# lighting_schematic.net
KiCad netlist of a schematic drawn in EasyEDA
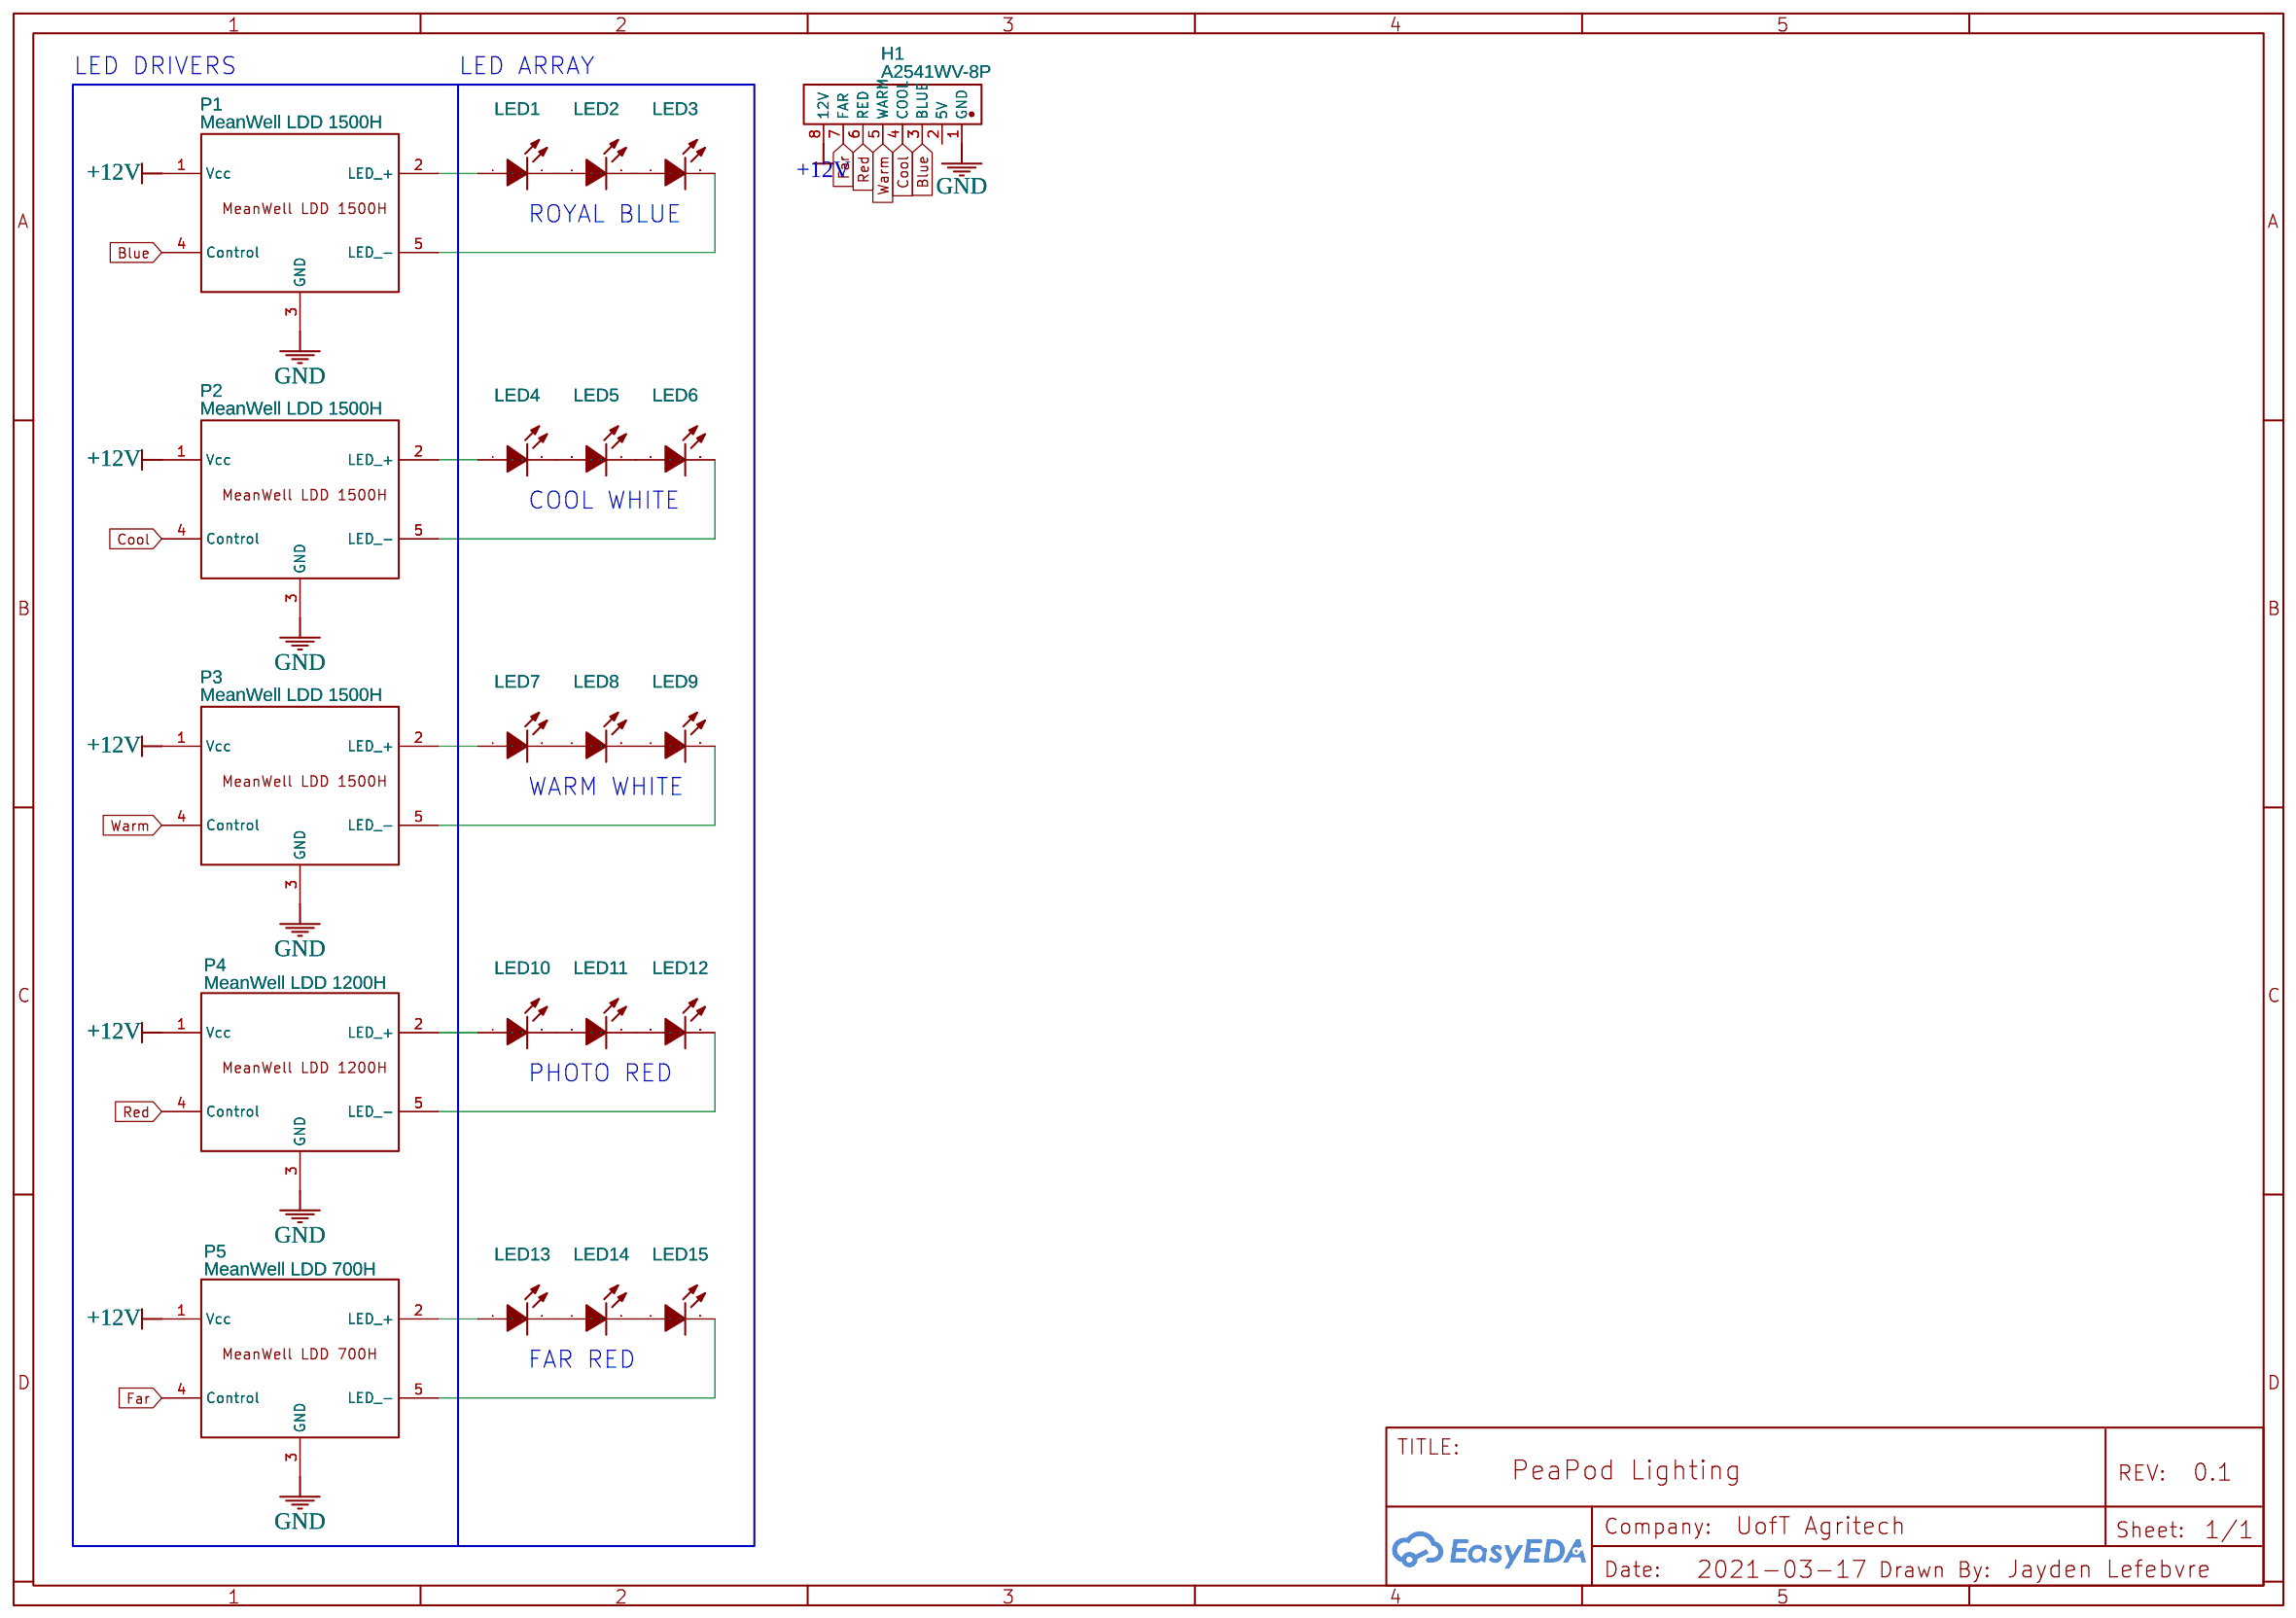
[diagram p0: schematic sheet]

(export (version "E")
  (design (tool "Eeschema 10.0.6"))
  (components
    (comp (ref "H1")
      (value "A2541WV-8P")
      (fields (field (name "BOM_Supplier Part") "C225483"))
      (libsource (lib "") (part "A2541WV-8P"))
    )
    (comp (ref "LED1")
      (value "XLAMP XP-G3 LED")
      (fields (field (name "BOM_Manufacturer Part") "XPGDWT-01-0000-00ME3"))
      (libsource (lib "") (part "XLAMP XP-G3 LED"))
    )
    (comp (ref "LED2")
      (value "XLAMP XP-G3 LED")
      (fields (field (name "BOM_Manufacturer Part") "XPGDWT-01-0000-00ME3"))
      (libsource (lib "") (part "XLAMP XP-G3 LED"))
    )
    (comp (ref "LED3")
      (value "XLAMP XP-G3 LED")
      (fields (field (name "BOM_Manufacturer Part") "XPGDWT-01-0000-00ME3"))
      (libsource (lib "") (part "XLAMP XP-G3 LED"))
    )
    (comp (ref "LED4")
      (value "XLAMP XP-G3 LED")
      (fields (field (name "BOM_Manufacturer Part") "XPGDWT-01-0000-00ME3"))
      (libsource (lib "") (part "XLAMP XP-G3 LED"))
    )
    (comp (ref "LED5")
      (value "XLAMP XP-G3 LED")
      (fields (field (name "BOM_Manufacturer Part") "XPGDWT-01-0000-00ME3"))
      (libsource (lib "") (part "XLAMP XP-G3 LED"))
    )
    (comp (ref "LED6")
      (value "XLAMP XP-G3 LED")
      (fields (field (name "BOM_Manufacturer Part") "XPGDWT-01-0000-00ME3"))
      (libsource (lib "") (part "XLAMP XP-G3 LED"))
    )
    (comp (ref "LED7")
      (value "XLAMP XP-G3 LED")
      (fields (field (name "BOM_Manufacturer Part") "XPGDWT-01-0000-00ME3"))
      (libsource (lib "") (part "XLAMP XP-G3 LED"))
    )
    (comp (ref "LED8")
      (value "XLAMP XP-G3 LED")
      (fields (field (name "BOM_Manufacturer Part") "XPGDWT-01-0000-00ME3"))
      (libsource (lib "") (part "XLAMP XP-G3 LED"))
    )
    (comp (ref "LED9")
      (value "XLAMP XP-G3 LED")
      (fields (field (name "BOM_Manufacturer Part") "XPGDWT-01-0000-00ME3"))
      (libsource (lib "") (part "XLAMP XP-G3 LED"))
    )
    (comp (ref "LED10")
      (value "XLAMP XP-G3 LED")
      (fields (field (name "BOM_Manufacturer Part") "XPGDWT-01-0000-00ME3"))
      (libsource (lib "") (part "XLAMP XP-G3 LED"))
    )
    (comp (ref "LED11")
      (value "XLAMP XP-G3 LED")
      (fields (field (name "BOM_Manufacturer Part") "XPGDWT-01-0000-00ME3"))
      (libsource (lib "") (part "XLAMP XP-G3 LED"))
    )
    (comp (ref "LED12")
      (value "XLAMP XP-G3 LED")
      (fields (field (name "BOM_Manufacturer Part") "XPGDWT-01-0000-00ME3"))
      (libsource (lib "") (part "XLAMP XP-G3 LED"))
    )
    (comp (ref "LED13")
      (value "XLAMP XP-G3 LED")
      (fields (field (name "BOM_Manufacturer Part") "XPGDWT-01-0000-00ME3"))
      (libsource (lib "") (part "XLAMP XP-G3 LED"))
    )
    (comp (ref "LED14")
      (value "XLAMP XP-G3 LED")
      (fields (field (name "BOM_Manufacturer Part") "XPGDWT-01-0000-00ME3"))
      (libsource (lib "") (part "XLAMP XP-G3 LED"))
    )
    (comp (ref "LED15")
      (value "XLAMP XP-G3 LED")
      (fields (field (name "BOM_Manufacturer Part") "XPGDWT-01-0000-00ME3"))
      (libsource (lib "") (part "XLAMP XP-G3 LED"))
    )
    (comp (ref "P1")
      (value "MeanWell LDD 1500H")
      (fields
        (field (name "BOM_Manufacturer Part") "LDD-1500H")
        (field (name "BOM_Supplier Part") "1866-3099-ND")
      )
      (libsource (lib "") (part "MeanWell LDD 1500H"))
    )
    (comp (ref "P2")
      (value "MeanWell LDD 1500H")
      (fields
        (field (name "BOM_Manufacturer Part") "LDD-1500H")
        (field (name "BOM_Supplier Part") "1866-3099-ND")
      )
      (libsource (lib "") (part "MeanWell LDD 1500H"))
    )
    (comp (ref "P3")
      (value "MeanWell LDD 1500H")
      (fields
        (field (name "BOM_Manufacturer Part") "LDD-1500H")
        (field (name "BOM_Supplier Part") "1866-3099-ND")
      )
      (libsource (lib "") (part "MeanWell LDD 1500H"))
    )
    (comp (ref "P4")
      (value "MeanWell LDD 1200H")
      (fields
        (field (name "BOM_Manufacturer Part") "LDD-1200H")
        (field (name "BOM_Supplier Part") "1866-3095-ND")
      )
      (libsource (lib "") (part "MeanWell LDD 1200H"))
    )
    (comp (ref "P5")
      (value "MeanWell LDD 700H")
      (fields
        (field (name "BOM_Manufacturer Part") "LDD-700H")
        (field (name "BOM_Supplier Part") "1866-3119-ND")
      )
      (libsource (lib "") (part "MeanWell LDD 700H"))
    )
  )
  (nets
    (net (code "1") (name "+12V") (class "Default")
      (node (ref "H1") (pin "8") (pinfunction "12V_8") (pintype "unspecified"))
      (node (ref "P1") (pin "1") (pinfunction "Vcc_1") (pintype "unspecified"))
      (node (ref "P2") (pin "1") (pinfunction "Vcc_1") (pintype "unspecified"))
      (node (ref "P3") (pin "1") (pinfunction "Vcc_1") (pintype "unspecified"))
      (node (ref "P4") (pin "1") (pinfunction "Vcc_1") (pintype "unspecified"))
      (node (ref "P5") (pin "1") (pinfunction "Vcc_1") (pintype "unspecified"))
    )
    (net (code "2") (name "Blue") (class "Default")
      (node (ref "H1") (pin "3") (pinfunction "BLUE_3") (pintype "unspecified"))
      (node (ref "P1") (pin "4") (pinfunction "Control_4") (pintype "unspecified"))
    )
    (net (code "3") (name "Cool") (class "Default")
      (node (ref "H1") (pin "4") (pinfunction "COOL_4") (pintype "unspecified"))
      (node (ref "P2") (pin "4") (pinfunction "Control_4") (pintype "unspecified"))
    )
    (net (code "4") (name "Far") (class "Default")
      (node (ref "H1") (pin "7") (pinfunction "FAR_7") (pintype "unspecified"))
      (node (ref "P5") (pin "4") (pinfunction "Control_4") (pintype "unspecified"))
    )
    (net (code "5") (name "GND") (class "Default")
      (node (ref "H1") (pin "1") (pinfunction "GND_1") (pintype "unspecified"))
      (node (ref "P1") (pin "3") (pinfunction "GND_3") (pintype "unspecified"))
      (node (ref "P2") (pin "3") (pinfunction "GND_3") (pintype "unspecified"))
      (node (ref "P3") (pin "3") (pinfunction "GND_3") (pintype "unspecified"))
      (node (ref "P4") (pin "3") (pinfunction "GND_3") (pintype "unspecified"))
      (node (ref "P5") (pin "3") (pinfunction "GND_3") (pintype "unspecified"))
    )
    (net (code "6") (name "Net-(LED1-A)") (class "Default")
      (node (ref "LED1") (pin "1") (pinfunction "A_1") (pintype "unspecified"))
      (node (ref "P1") (pin "2") (pinfunction "LED_+_2") (pintype "unspecified"))
    )
    (net (code "7") (name "Net-(LED1-K)") (class "Default")
      (node (ref "LED1") (pin "2") (pinfunction "K_2") (pintype "unspecified"))
      (node (ref "LED2") (pin "1") (pinfunction "A_1") (pintype "unspecified"))
    )
    (net (code "8") (name "Net-(LED2-K)") (class "Default")
      (node (ref "LED2") (pin "2") (pinfunction "K_2") (pintype "unspecified"))
      (node (ref "LED3") (pin "1") (pinfunction "A_1") (pintype "unspecified"))
    )
    (net (code "9") (name "Net-(LED3-K)") (class "Default")
      (node (ref "LED3") (pin "2") (pinfunction "K_2") (pintype "unspecified"))
      (node (ref "P1") (pin "5") (pinfunction "LED_-_5") (pintype "unspecified"))
    )
    (net (code "10") (name "Net-(LED4-A)") (class "Default")
      (node (ref "LED4") (pin "1") (pinfunction "A_1") (pintype "unspecified"))
      (node (ref "P2") (pin "2") (pinfunction "LED_+_2") (pintype "unspecified"))
    )
    (net (code "11") (name "Net-(LED4-K)") (class "Default")
      (node (ref "LED4") (pin "2") (pinfunction "K_2") (pintype "unspecified"))
      (node (ref "LED5") (pin "1") (pinfunction "A_1") (pintype "unspecified"))
    )
    (net (code "12") (name "Net-(LED5-K)") (class "Default")
      (node (ref "LED5") (pin "2") (pinfunction "K_2") (pintype "unspecified"))
      (node (ref "LED6") (pin "1") (pinfunction "A_1") (pintype "unspecified"))
    )
    (net (code "13") (name "Net-(LED6-K)") (class "Default")
      (node (ref "LED6") (pin "2") (pinfunction "K_2") (pintype "unspecified"))
      (node (ref "P2") (pin "5") (pinfunction "LED_-_5") (pintype "unspecified"))
    )
    (net (code "14") (name "Net-(LED7-A)") (class "Default")
      (node (ref "LED7") (pin "1") (pinfunction "A_1") (pintype "unspecified"))
      (node (ref "P3") (pin "2") (pinfunction "LED_+_2") (pintype "unspecified"))
    )
    (net (code "15") (name "Net-(LED7-K)") (class "Default")
      (node (ref "LED7") (pin "2") (pinfunction "K_2") (pintype "unspecified"))
      (node (ref "LED8") (pin "1") (pinfunction "A_1") (pintype "unspecified"))
    )
    (net (code "16") (name "Net-(LED8-K)") (class "Default")
      (node (ref "LED8") (pin "2") (pinfunction "K_2") (pintype "unspecified"))
      (node (ref "LED9") (pin "1") (pinfunction "A_1") (pintype "unspecified"))
    )
    (net (code "17") (name "Net-(LED9-K)") (class "Default")
      (node (ref "LED9") (pin "2") (pinfunction "K_2") (pintype "unspecified"))
      (node (ref "P3") (pin "5") (pinfunction "LED_-_5") (pintype "unspecified"))
    )
    (net (code "18") (name "Net-(LED10-A)") (class "Default")
      (node (ref "LED10") (pin "1") (pinfunction "A_1") (pintype "unspecified"))
      (node (ref "P4") (pin "2") (pinfunction "LED_+_2") (pintype "unspecified"))
    )
    (net (code "19") (name "Net-(LED10-K)") (class "Default")
      (node (ref "LED10") (pin "2") (pinfunction "K_2") (pintype "unspecified"))
      (node (ref "LED11") (pin "1") (pinfunction "A_1") (pintype "unspecified"))
    )
    (net (code "20") (name "Net-(LED11-K)") (class "Default")
      (node (ref "LED11") (pin "2") (pinfunction "K_2") (pintype "unspecified"))
      (node (ref "LED12") (pin "1") (pinfunction "A_1") (pintype "unspecified"))
    )
    (net (code "21") (name "Net-(LED12-K)") (class "Default")
      (node (ref "LED12") (pin "2") (pinfunction "K_2") (pintype "unspecified"))
      (node (ref "P4") (pin "5") (pinfunction "LED_-_5") (pintype "unspecified"))
    )
    (net (code "22") (name "Net-(LED13-A)") (class "Default")
      (node (ref "LED13") (pin "1") (pinfunction "A_1") (pintype "unspecified"))
      (node (ref "P5") (pin "2") (pinfunction "LED_+_2") (pintype "unspecified"))
    )
    (net (code "23") (name "Net-(LED13-K)") (class "Default")
      (node (ref "LED13") (pin "2") (pinfunction "K_2") (pintype "unspecified"))
      (node (ref "LED14") (pin "1") (pinfunction "A_1") (pintype "unspecified"))
    )
    (net (code "24") (name "Net-(LED14-K)") (class "Default")
      (node (ref "LED14") (pin "2") (pinfunction "K_2") (pintype "unspecified"))
      (node (ref "LED15") (pin "1") (pinfunction "A_1") (pintype "unspecified"))
    )
    (net (code "25") (name "Net-(LED15-K)") (class "Default")
      (node (ref "LED15") (pin "2") (pinfunction "K_2") (pintype "unspecified"))
      (node (ref "P5") (pin "5") (pinfunction "LED_-_5") (pintype "unspecified"))
    )
    (net (code "26") (name "Red") (class "Default")
      (node (ref "H1") (pin "6") (pinfunction "RED_6") (pintype "unspecified"))
      (node (ref "P4") (pin "4") (pinfunction "Control_4") (pintype "unspecified"))
    )
    (net (code "27") (name "Warm") (class "Default")
      (node (ref "H1") (pin "5") (pinfunction "WARM_5") (pintype "unspecified"))
      (node (ref "P3") (pin "4") (pinfunction "Control_4") (pintype "unspecified"))
    )
    (net (code "28") (name "unconnected-(H1-5V-Pad2)") (class "Default")
      (node (ref "H1") (pin "2") (pinfunction "5V_2") (pintype "unspecified"))
    )
  )
)
